# Main.net
KiCad netlist of a schematic drawn in Altium Designer
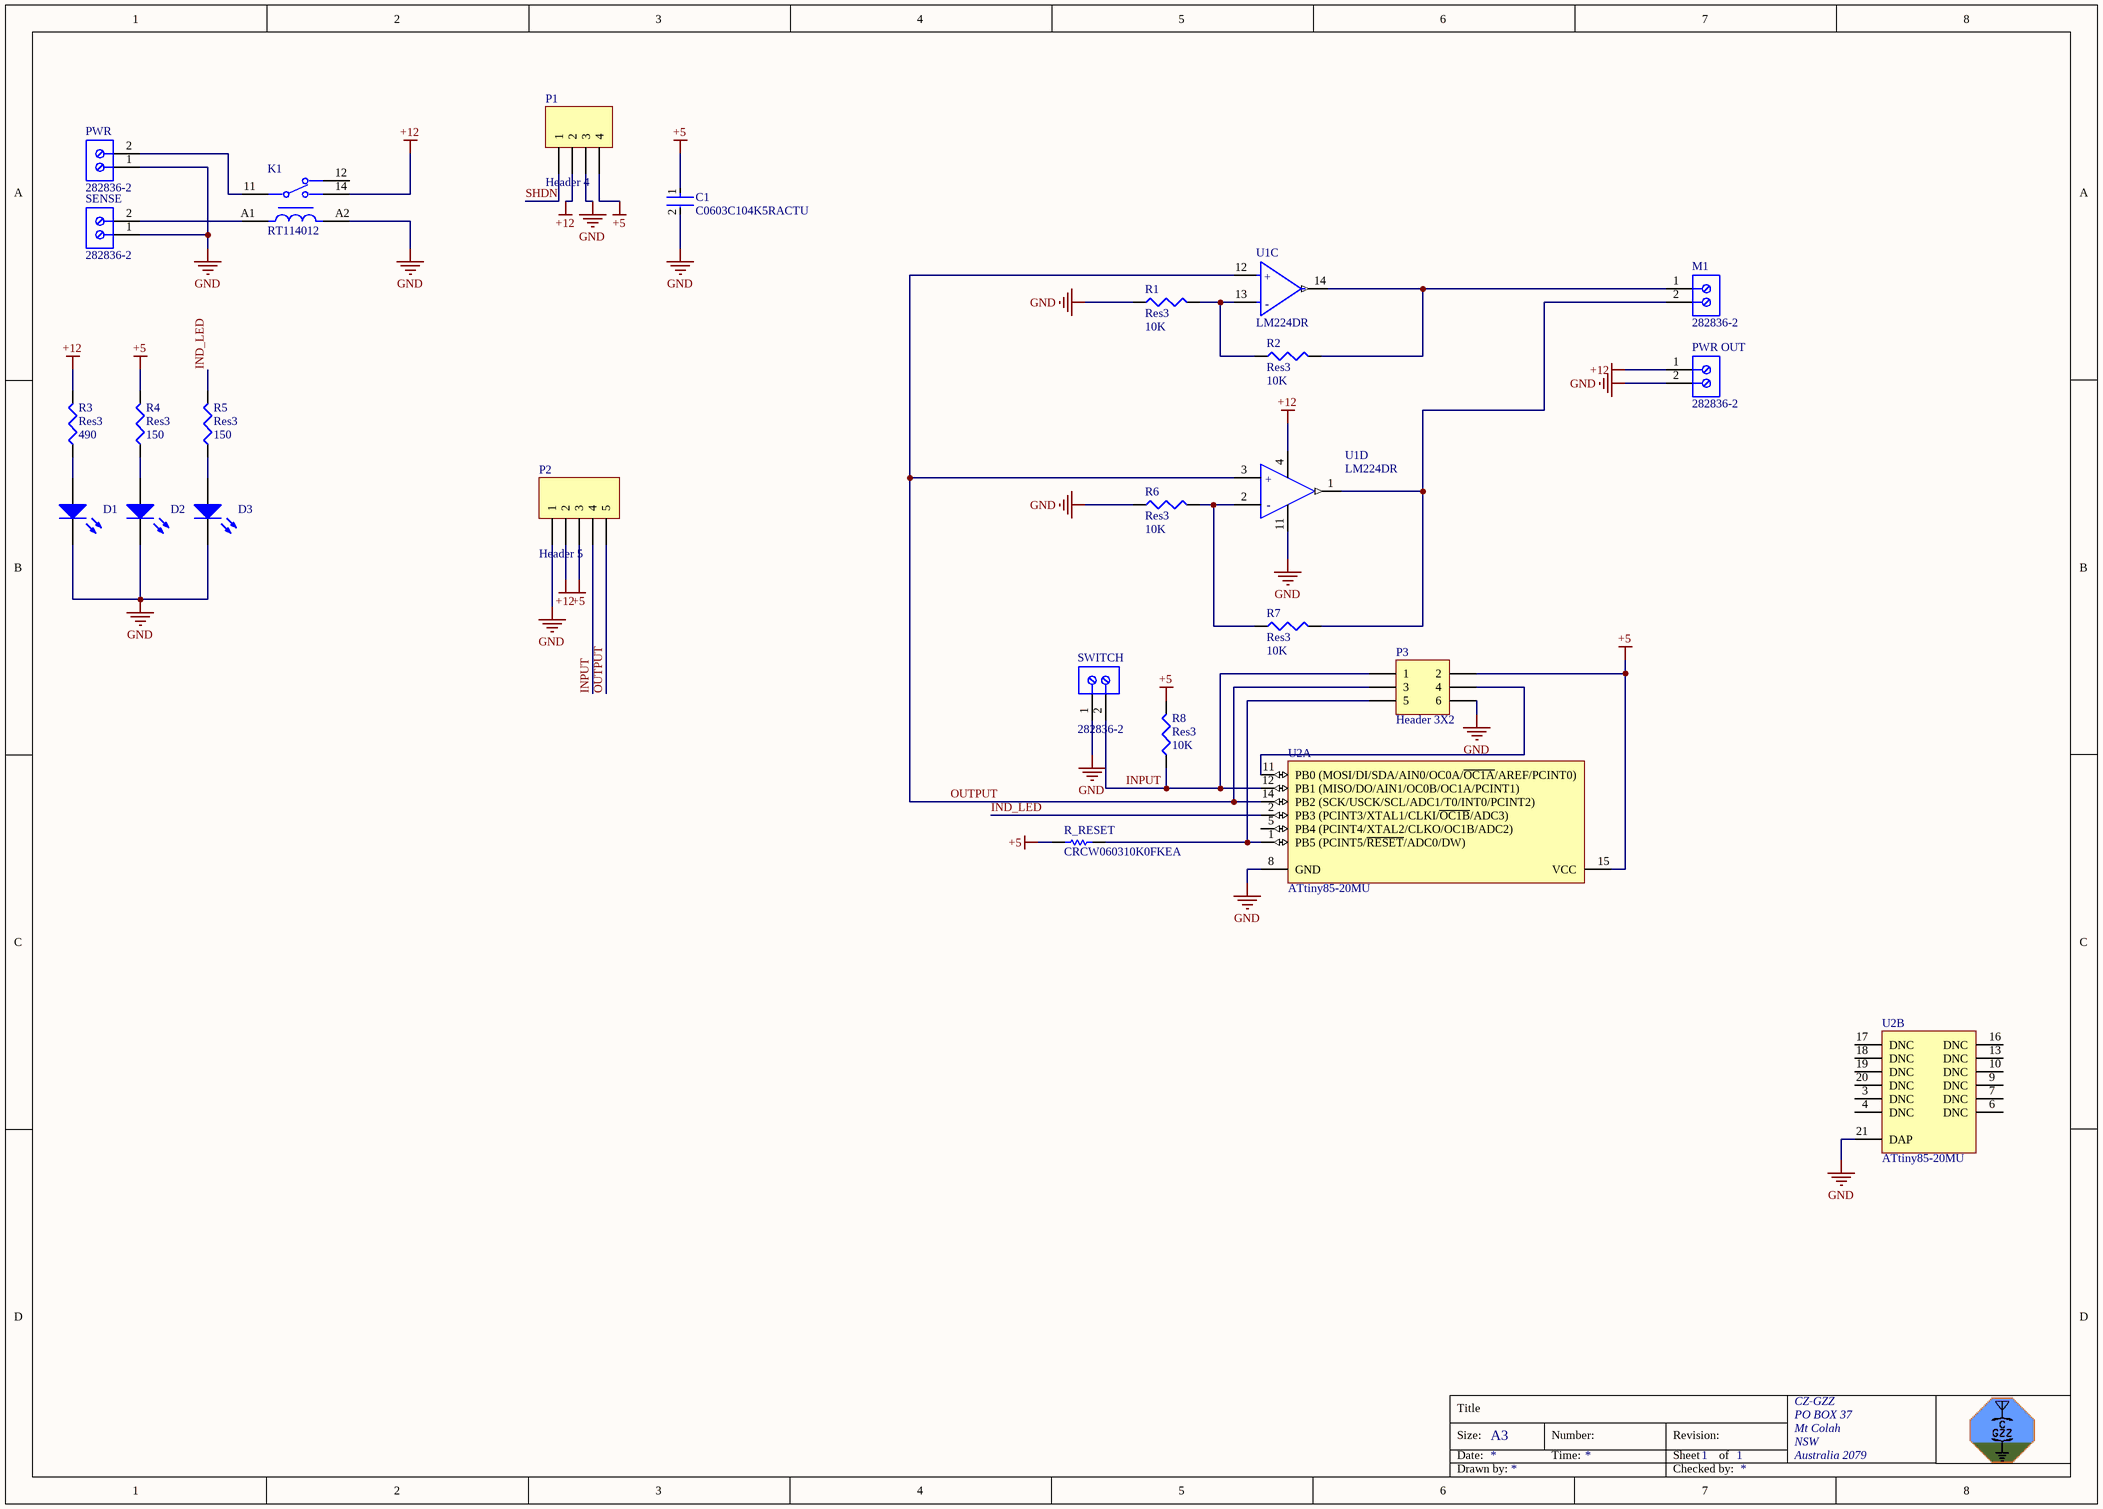
[diagram p0: Main.SchDoc]

(export (version "E")
  (design (tool "Eeschema 10.0.6"))
  (components
    (comp (ref "C1")
      (value "C0603C104K5RACTU")
      (footprint "FP-C0603C-CF-MFG")
      (description "CAP CER 0.1UF 50V X7R 0603")
      (fields (field (name "TOLERANCE") "0.1") (field (name "MANUFACTURER") "KEMET"))
      (libsource (lib "Altium Content Vault") (part "b4654b650e69147ec39a6b967a45e02"))
    )
    (comp (ref "D1")
      (value "LED2")
      (footprint "3.2X1.6X1.1")
      (description "Typical RED, GREEN, YELLOW, AMBER GaAs LED")
      (fields (field (name "PUBLISHER") "Altium Limited"))
      (libsource (lib "Miscellaneous Devices") (part "LED2"))
    )
    (comp (ref "D2")
      (value "LED2")
      (footprint "3.2X1.6X1.1")
      (description "Typical RED, GREEN, YELLOW, AMBER GaAs LED")
      (fields (field (name "PUBLISHER") "Altium Limited"))
      (libsource (lib "Miscellaneous Devices") (part "LED2"))
    )
    (comp (ref "D3")
      (value "LED2")
      (footprint "3.2X1.6X1.1")
      (description "Typical RED, GREEN, YELLOW, AMBER GaAs LED")
      (fields (field (name "PUBLISHER") "Altium Limited"))
      (libsource (lib "Miscellaneous Devices") (part "LED2"))
    )
    (comp (ref "K1")
      (value "RT114012")
      (footprint "FP-RT114012-MFG")
      (description "RELAY GEN PURPOSE SPDT 12A 12V")
      (fields
        (field (name "OCTOPART") "https://octopart.com/rt114012-te+connectivity-39636422")
        (field (name "MANUFACTURER") "TE Connectivity")
      )
      (libsource (lib "Altium Content Vault") (part "073c63e877000fb1b84f95b80705c0f"))
    )
    (comp (ref "M1")
      (value "282836-2")
      (footprint "TECO-282836-2_V")
      (description "Female Header, Pitch 5 mm, 1 x 2 Position, Height 10 mm, Tail Length 3.5 mm, Rohs, Bulk")
      (fields (field (name "VOLTAGE") "300V") (field (name "MANUFACTURER") "TE Connectivity"))
      (libsource (lib "Altium Content Vault") (part "CN-1P-F-TB2"))
    )
    (comp (ref "P1")
      (value "Header 4")
      (footprint "HDR1X4")
      (description "Header, 4-Pin")
      (fields (field (name "PUBLISHER") "Altium Limited"))
      (libsource (lib "Miscellaneous Connectors") (part "Header 4"))
    )
    (comp (ref "P2")
      (value "Header 5")
      (footprint "HDR1X5")
      (description "Header, 5-Pin")
      (fields (field (name "PUBLISHER") "Altium Limited"))
      (libsource (lib "Miscellaneous Connectors") (part "Header 5"))
    )
    (comp (ref "P3")
      (value "Header 3X2")
      (footprint "HDR2X3")
      (description "Header, 3-Pin, Dual row")
      (fields (field (name "PUBLISHER") "Altium Limited"))
      (libsource (lib "Miscellaneous Connectors") (part "Header 3X2"))
    )
    (comp (ref "PWR")
      (value "282836-2")
      (footprint "TECO-282836-2_V")
      (description "Female Header, Pitch 5 mm, 1 x 2 Position, Height 10 mm, Tail Length 3.5 mm, Rohs, Bulk")
      (fields (field (name "VOLTAGE") "300V") (field (name "MANUFACTURER") "TE Connectivity"))
      (libsource (lib "Altium Content Vault") (part "CN-1P-F-TB2"))
    )
    (comp (ref "PWR OUT")
      (value "282836-2")
      (footprint "TECO-282836-2_V")
      (description "Female Header, Pitch 5 mm, 1 x 2 Position, Height 10 mm, Tail Length 3.5 mm, Rohs, Bulk")
      (fields (field (name "VOLTAGE") "300V") (field (name "MANUFACTURER") "TE Connectivity"))
      (libsource (lib "Altium Content Vault") (part "CN-1P-F-TB2"))
    )
    (comp (ref "R1")
      (value "Res3")
      (footprint "J1-0603")
      (description "Resistor")
      (fields (field (name "ALTIUM_VALUE") "10K") (field (name "PUBLISHER") "Altium Limited"))
      (libsource (lib "Miscellaneous Devices") (part "Res3"))
    )
    (comp (ref "R2")
      (value "Res3")
      (footprint "J1-0603")
      (description "Resistor")
      (fields (field (name "ALTIUM_VALUE") "10K") (field (name "PUBLISHER") "Altium Limited"))
      (libsource (lib "Miscellaneous Devices") (part "Res3"))
    )
    (comp (ref "R3")
      (value "Res3")
      (footprint "J1-0603")
      (description "Resistor")
      (fields (field (name "ALTIUM_VALUE") "490") (field (name "PUBLISHER") "Altium Limited"))
      (libsource (lib "Miscellaneous Devices") (part "Res3"))
    )
    (comp (ref "R4")
      (value "Res3")
      (footprint "J1-0603")
      (description "Resistor")
      (fields (field (name "ALTIUM_VALUE") "150") (field (name "PUBLISHER") "Altium Limited"))
      (libsource (lib "Miscellaneous Devices") (part "Res3"))
    )
    (comp (ref "R5")
      (value "Res3")
      (footprint "J1-0603")
      (description "Resistor")
      (fields (field (name "ALTIUM_VALUE") "150") (field (name "PUBLISHER") "Altium Limited"))
      (libsource (lib "Miscellaneous Devices") (part "Res3"))
    )
    (comp (ref "R6")
      (value "Res3")
      (footprint "J1-0603")
      (description "Resistor")
      (fields (field (name "ALTIUM_VALUE") "10K") (field (name "PUBLISHER") "Altium Limited"))
      (libsource (lib "Miscellaneous Devices") (part "Res3"))
    )
    (comp (ref "R7")
      (value "Res3")
      (footprint "J1-0603")
      (description "Resistor")
      (fields (field (name "ALTIUM_VALUE") "10K") (field (name "PUBLISHER") "Altium Limited"))
      (libsource (lib "Miscellaneous Devices") (part "Res3"))
    )
    (comp (ref "R8")
      (value "Res3")
      (footprint "J1-0603")
      (description "Resistor")
      (fields (field (name "ALTIUM_VALUE") "10K") (field (name "PUBLISHER") "Altium Limited"))
      (libsource (lib "Miscellaneous Devices") (part "Res3"))
    )
    (comp (ref "R_RESET")
      (value "CRCW060310K0FKEA")
      (footprint "RESC1609X50X30NL8T20")
      (description "Chip Resistor, 10 KOhm, +/- 1%, 100 mW, -55 to 155 degC, 0603 (1608 Metric), RoHS, Tape and Reel")
      (fields (field (name "MANUFACTURER") "Vishay Semiconductor"))
      (libsource (lib "Altium Content Vault") (part "RES-2"))
    )
    (comp (ref "SENSE")
      (value "282836-2")
      (footprint "TECO-282836-2_V")
      (description "Female Header, Pitch 5 mm, 1 x 2 Position, Height 10 mm, Tail Length 3.5 mm, Rohs, Bulk")
      (fields (field (name "VOLTAGE") "300V") (field (name "MANUFACTURER") "TE Connectivity"))
      (libsource (lib "Altium Content Vault") (part "CN-1P-F-TB2"))
    )
    (comp (ref "SWITCH")
      (value "282836-2")
      (footprint "TECO-282836-2_V")
      (description "Female Header, Pitch 5 mm, 1 x 2 Position, Height 10 mm, Tail Length 3.5 mm, Rohs, Bulk")
      (fields (field (name "VOLTAGE") "300V") (field (name "MANUFACTURER") "TE Connectivity"))
      (libsource (lib "Altium Content Vault") (part "CN-1P-F-TB2"))
    )
    (comp (ref "U1")
      (value "LM224DR")
      (footprint "FP-D0014A-IPC_C")
      (description "IC OPAMP GP 4 CIRCUIT 14SOIC")
      (libsource (lib "Altium Content Vault") (part "bb9f81a046b623eda4e2adff985266b"))
    )
    (comp (ref "U2")
      (value "ATtiny85-20MU")
      (footprint "20M1_N")
      (libsource (lib "Altium Content Vault") (part "MC-8B-ATT25-SQ21"))
    )
  )
  (nets
    (net (code "1") (name "+5") (class "Default")
      (node (ref "C1") (pin "1") (pinfunction "1_1") (pintype "passive"))
      (node (ref "P1") (pin "4") (pinfunction "4_4") (pintype "passive"))
      (node (ref "P2") (pin "3") (pinfunction "3_3") (pintype "passive"))
      (node (ref "P3") (pin "2") (pinfunction "2_2") (pintype "passive"))
      (node (ref "R4") (pin "2") (pinfunction "2_2") (pintype "passive"))
      (node (ref "R8") (pin "2") (pinfunction "2_2") (pintype "passive"))
      (node (ref "R_RESET") (pin "2") (pinfunction "2_2") (pintype "passive"))
      (node (ref "U2") (pin "15") (pinfunction "VCC_15") (pintype "power_in"))
    )
    (net (code "2") (name "+12") (class "Default")
      (node (ref "K1") (pin "14") (pinfunction "14_14") (pintype "passive"))
      (node (ref "P1") (pin "2") (pinfunction "2_2") (pintype "passive"))
      (node (ref "P2") (pin "2") (pinfunction "2_2") (pintype "passive"))
      (node (ref "PWR OUT") (pin "1") (pinfunction "1_1") (pintype "passive"))
      (node (ref "R3") (pin "2") (pinfunction "2_2") (pintype "passive"))
      (node (ref "U1") (pin "4") (pinfunction "VCC_4") (pintype "passive"))
    )
    (net (code "3") (name "/IND_LED") (class "Default")
      (node (ref "R5") (pin "2") (pinfunction "2_2") (pintype "passive"))
      (node (ref "U2") (pin "2") (pinfunction "PB3_(PCINT3/XTAL1/CLKI/~{OC1B}/ADC3)_2") (pintype "bidirectional"))
    )
    (net (code "4") (name "/INPUT") (class "Default")
      (node (ref "P2") (pin "4") (pinfunction "4_4") (pintype "passive"))
      (node (ref "P3") (pin "1") (pinfunction "1_1") (pintype "passive"))
      (node (ref "R8") (pin "1") (pinfunction "1_1") (pintype "passive"))
      (node (ref "SWITCH") (pin "2") (pinfunction "2_2") (pintype "passive"))
      (node (ref "U2") (pin "12") (pinfunction "PB1_(MISO/DO/AIN1/OC0B/OC1A/PCINT1)_12") (pintype "bidirectional"))
    )
    (net (code "5") (name "/OUTPUT") (class "Default")
      (node (ref "P2") (pin "5") (pinfunction "5_5") (pintype "passive"))
      (node (ref "P3") (pin "3") (pinfunction "3_3") (pintype "passive"))
      (node (ref "U1") (pin "12") (pinfunction "4IN+_12") (pintype "tri_state"))
      (node (ref "U1") (pin "3") (pinfunction "1IN+_3") (pintype "tri_state"))
      (node (ref "U2") (pin "14") (pinfunction "PB2_(SCK/USCK/SCL/ADC1/T0/INT0/PCINT2)_14") (pintype "bidirectional"))
    )
    (net (code "6") (name "/SHDN") (class "Default")
      (node (ref "P1") (pin "1") (pinfunction "1_1") (pintype "passive"))
    )
    (net (code "7") (name "GND") (class "Default")
      (node (ref "C1") (pin "2") (pinfunction "2_2") (pintype "passive"))
      (node (ref "D1") (pin "2") (pinfunction "K_2") (pintype "passive"))
      (node (ref "D2") (pin "2") (pinfunction "K_2") (pintype "passive"))
      (node (ref "D3") (pin "2") (pinfunction "K_2") (pintype "passive"))
      (node (ref "K1") (pin "A2") (pinfunction "A2_A2") (pintype "passive"))
      (node (ref "P1") (pin "3") (pinfunction "3_3") (pintype "passive"))
      (node (ref "P2") (pin "1") (pinfunction "1_1") (pintype "passive"))
      (node (ref "P3") (pin "6") (pinfunction "6_6") (pintype "passive"))
      (node (ref "PWR") (pin "1") (pinfunction "1_1") (pintype "passive"))
      (node (ref "PWR OUT") (pin "2") (pinfunction "2_2") (pintype "passive"))
      (node (ref "R1") (pin "1") (pinfunction "1_1") (pintype "passive"))
      (node (ref "R6") (pin "1") (pinfunction "1_1") (pintype "passive"))
      (node (ref "SENSE") (pin "1") (pinfunction "1_1") (pintype "passive"))
      (node (ref "SWITCH") (pin "1") (pinfunction "1_1") (pintype "passive"))
      (node (ref "U1") (pin "11") (pinfunction "GND_11") (pintype "power_in"))
      (node (ref "U2") (pin "21") (pinfunction "DAP_21") (pintype "passive"))
      (node (ref "U2") (pin "8") (pinfunction "GND_8") (pintype "power_in"))
    )
    (net (code "8") (name "Net-(D1-A)") (class "Default")
      (node (ref "D1") (pin "1") (pinfunction "A_1") (pintype "passive"))
      (node (ref "R3") (pin "1") (pinfunction "1_1") (pintype "passive"))
    )
    (net (code "9") (name "Net-(D2-A)") (class "Default")
      (node (ref "D2") (pin "1") (pinfunction "A_1") (pintype "passive"))
      (node (ref "R4") (pin "1") (pinfunction "1_1") (pintype "passive"))
    )
    (net (code "10") (name "Net-(D3-A)") (class "Default")
      (node (ref "D3") (pin "1") (pinfunction "A_1") (pintype "passive"))
      (node (ref "R5") (pin "1") (pinfunction "1_1") (pintype "passive"))
    )
    (net (code "11") (name "Net-(K1-Pad11)") (class "Default")
      (node (ref "K1") (pin "11") (pinfunction "11_11") (pintype "passive"))
      (node (ref "PWR") (pin "2") (pinfunction "2_2") (pintype "passive"))
    )
    (net (code "12") (name "Net-(K1-PadA1)") (class "Default")
      (node (ref "K1") (pin "A1") (pinfunction "A1_A1") (pintype "passive"))
      (node (ref "SENSE") (pin "2") (pinfunction "2_2") (pintype "passive"))
    )
    (net (code "13") (name "Net-(U1C-4IN-)") (class "Default")
      (node (ref "R1") (pin "2") (pinfunction "2_2") (pintype "passive"))
      (node (ref "R2") (pin "1") (pinfunction "1_1") (pintype "passive"))
      (node (ref "U1") (pin "13") (pinfunction "4IN-_13") (pintype "tri_state"))
    )
    (net (code "14") (name "Net-(U1C-4OUT)") (class "Default")
      (node (ref "M1") (pin "1") (pinfunction "1_1") (pintype "passive"))
      (node (ref "R2") (pin "2") (pinfunction "2_2") (pintype "passive"))
      (node (ref "U1") (pin "14") (pinfunction "4OUT_14") (pintype "output"))
    )
    (net (code "15") (name "Net-(U1D-1IN-)") (class "Default")
      (node (ref "R6") (pin "2") (pinfunction "2_2") (pintype "passive"))
      (node (ref "R7") (pin "1") (pinfunction "1_1") (pintype "passive"))
      (node (ref "U1") (pin "2") (pinfunction "1IN-_2") (pintype "tri_state"))
    )
    (net (code "16") (name "Net-(U1D-1OUT)") (class "Default")
      (node (ref "M1") (pin "2") (pinfunction "2_2") (pintype "passive"))
      (node (ref "R7") (pin "2") (pinfunction "2_2") (pintype "passive"))
      (node (ref "U1") (pin "1") (pinfunction "1OUT_1") (pintype "output"))
    )
    (net (code "17") (name "Net-(U2A-PB0_(MOSI{slash}DI{slash}SDA{slash}AIN0{slash}OC0A{slash}~{OC1A}{slash}AREF{slash}PCINT0))") (class "Default")
      (node (ref "P3") (pin "4") (pinfunction "4_4") (pintype "passive"))
      (node (ref "U2") (pin "11") (pinfunction "PB0_(MOSI/DI/SDA/AIN0/OC0A/~{OC1A}/AREF/PCINT0)_11") (pintype "bidirectional"))
    )
    (net (code "18") (name "Net-(U2A-PB5_(PCINT5{slash}~{RESET}{slash}ADC0{slash}DW))") (class "Default")
      (node (ref "P3") (pin "5") (pinfunction "5_5") (pintype "passive"))
      (node (ref "R_RESET") (pin "1") (pinfunction "1_1") (pintype "passive"))
      (node (ref "U2") (pin "1") (pinfunction "PB5_(PCINT5/~{RESET}/ADC0/DW)_1") (pintype "bidirectional"))
    )
    (net (code "19") (name "unconnected-(K1-Pad12)") (class "Default")
      (node (ref "K1") (pin "12") (pinfunction "12_12") (pintype "passive"))
    )
    (net (code "20") (name "unconnected-(U2A-PB4_(PCINT4{slash}XTAL2{slash}CLKO{slash}OC1B{slash}ADC2)-Pad5)") (class "Default")
      (node (ref "U2") (pin "5") (pinfunction "PB4_(PCINT4/XTAL2/CLKO/OC1B/ADC2)_5") (pintype "bidirectional"))
    )
    (net (code "21") (name "unconnected-(U2B-DNC-Pad3)") (class "Default")
      (node (ref "U2") (pin "3") (pinfunction "DNC_3") (pintype "passive"))
    )
    (net (code "22") (name "unconnected-(U2B-DNC-Pad4)") (class "Default")
      (node (ref "U2") (pin "4") (pinfunction "DNC_4") (pintype "passive"))
    )
    (net (code "23") (name "unconnected-(U2B-DNC-Pad6)") (class "Default")
      (node (ref "U2") (pin "6") (pinfunction "DNC_6") (pintype "passive"))
    )
    (net (code "24") (name "unconnected-(U2B-DNC-Pad7)") (class "Default")
      (node (ref "U2") (pin "7") (pinfunction "DNC_7") (pintype "passive"))
    )
    (net (code "25") (name "unconnected-(U2B-DNC-Pad9)") (class "Default")
      (node (ref "U2") (pin "9") (pinfunction "DNC_9") (pintype "passive"))
    )
    (net (code "26") (name "unconnected-(U2B-DNC-Pad10)") (class "Default")
      (node (ref "U2") (pin "10") (pinfunction "DNC_10") (pintype "passive"))
    )
    (net (code "27") (name "unconnected-(U2B-DNC-Pad13)") (class "Default")
      (node (ref "U2") (pin "13") (pinfunction "DNC_13") (pintype "passive"))
    )
    (net (code "28") (name "unconnected-(U2B-DNC-Pad16)") (class "Default")
      (node (ref "U2") (pin "16") (pinfunction "DNC_16") (pintype "passive"))
    )
    (net (code "29") (name "unconnected-(U2B-DNC-Pad17)") (class "Default")
      (node (ref "U2") (pin "17") (pinfunction "DNC_17") (pintype "passive"))
    )
    (net (code "30") (name "unconnected-(U2B-DNC-Pad18)") (class "Default")
      (node (ref "U2") (pin "18") (pinfunction "DNC_18") (pintype "passive"))
    )
    (net (code "31") (name "unconnected-(U2B-DNC-Pad19)") (class "Default")
      (node (ref "U2") (pin "19") (pinfunction "DNC_19") (pintype "passive"))
    )
    (net (code "32") (name "unconnected-(U2B-DNC-Pad20)") (class "Default")
      (node (ref "U2") (pin "20") (pinfunction "DNC_20") (pintype "passive"))
    )
  )
)
